# db9smt-autoband.net
KiCad netlist of a schematic drawn in EAGLE
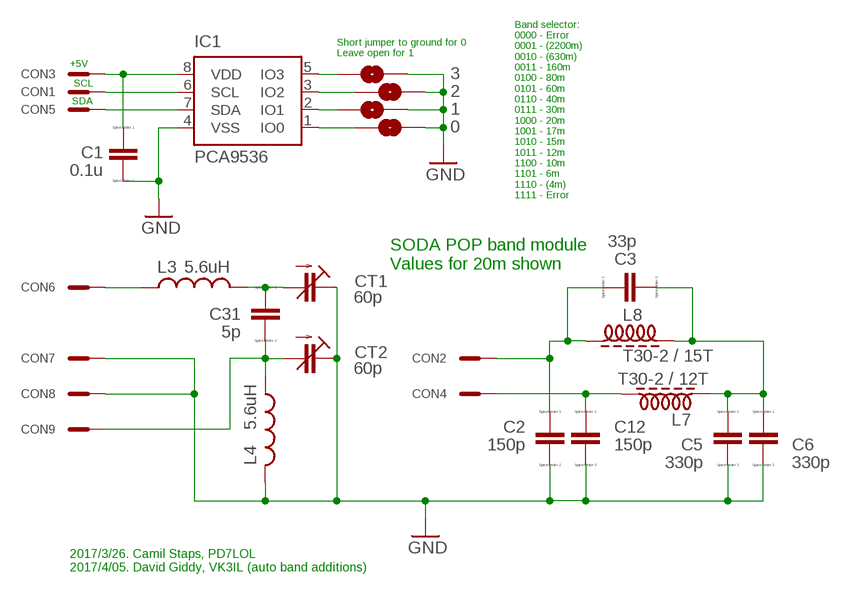
[diagram p0: schematic, sheet 1]

(export (version "E")
  (design (tool "Eeschema 10.0.6"))
  (components
    (comp (ref "0") (value "SJ") (footprint "eagle-import:SJ") (libsource (lib "eagle-import") (part "SJ")))
    (comp (ref "1") (value "SJ") (footprint "eagle-import:SJ") (libsource (lib "eagle-import") (part "SJ")))
    (comp (ref "2") (value "SJ") (footprint "eagle-import:SJ") (libsource (lib "eagle-import") (part "SJ")))
    (comp (ref "3") (value "SJ") (footprint "eagle-import:SJ") (libsource (lib "eagle-import") (part "SJ")))
    (comp (ref "C1")
      (value "0.1u")
      (footprint "eagle-import:C0603")
      (libsource (lib "eagle-import") (part "CC0603"))
    )
    (comp (ref "C2")
      (value "150p")
      (footprint "eagle-import:C0603")
      (libsource (lib "eagle-import") (part "CC0603"))
    )
    (comp (ref "C3")
      (value "33p")
      (footprint "eagle-import:C0603")
      (libsource (lib "eagle-import") (part "CC0603"))
    )
    (comp (ref "C5")
      (value "330p")
      (footprint "eagle-import:C0603")
      (libsource (lib "eagle-import") (part "CC0603"))
    )
    (comp (ref "C6")
      (value "330p")
      (footprint "eagle-import:C0603")
      (libsource (lib "eagle-import") (part "CC0603"))
    )
    (comp (ref "C12")
      (value "150p")
      (footprint "eagle-import:C0603")
      (libsource (lib "eagle-import") (part "CC0603"))
    )
    (comp (ref "C31")
      (value "5p")
      (footprint "eagle-import:C0603")
      (libsource (lib "eagle-import") (part "CC0603"))
    )
    (comp (ref "CON1")
      (value "PADONPRINT")
      (footprint "eagle-import:PAD")
      (libsource (lib "eagle-import") (part "PADONPRINT"))
    )
    (comp (ref "CON2")
      (value "PADONPRINT")
      (footprint "eagle-import:PAD")
      (libsource (lib "eagle-import") (part "PADONPRINT"))
    )
    (comp (ref "CON3")
      (value "PADONPRINT")
      (footprint "eagle-import:PAD")
      (libsource (lib "eagle-import") (part "PADONPRINT"))
    )
    (comp (ref "CON4")
      (value "PADONPRINT")
      (footprint "eagle-import:PAD")
      (libsource (lib "eagle-import") (part "PADONPRINT"))
    )
    (comp (ref "CON5")
      (value "PADONPRINT")
      (footprint "eagle-import:PAD")
      (libsource (lib "eagle-import") (part "PADONPRINT"))
    )
    (comp (ref "CON6")
      (value "PADONPRINT")
      (footprint "eagle-import:PAD")
      (libsource (lib "eagle-import") (part "PADONPRINT"))
    )
    (comp (ref "CON7")
      (value "PADONPRINT")
      (footprint "eagle-import:PAD")
      (libsource (lib "eagle-import") (part "PADONPRINT"))
    )
    (comp (ref "CON8")
      (value "PADONPRINT")
      (footprint "eagle-import:PAD")
      (libsource (lib "eagle-import") (part "PADONPRINT"))
    )
    (comp (ref "CON9")
      (value "PADONPRINT")
      (footprint "eagle-import:PAD")
      (libsource (lib "eagle-import") (part "PADONPRINT"))
    )
    (comp (ref "CT1")
      (value "60p")
      (footprint "eagle-import:CTRIMTZ03")
      (libsource (lib "eagle-import") (part "C-TRIMMTZ03"))
    )
    (comp (ref "CT2")
      (value "60p")
      (footprint "eagle-import:CTRIMTZ03")
      (libsource (lib "eagle-import") (part "C-TRIMMTZ03"))
    )
    (comp (ref "IC1")
      (value "PCA9536")
      (footprint "eagle-import:SO8")
      (libsource (lib "eagle-import") (part "PCA9536"))
    )
    (comp (ref "L3")
      (value "5.6uH")
      (footprint "eagle-import:L2012C")
      (libsource (lib "eagle-import") (part "L-USL2012C"))
    )
    (comp (ref "L4")
      (value "5.6uH")
      (footprint "eagle-import:L2012C")
      (libsource (lib "eagle-import") (part "L-USL2012C"))
    )
    (comp (ref "L7")
      (value "T30-2 / 12T")
      (footprint "eagle-import:T30-2-28AWG-15T")
      (libsource (lib "eagle-import") (part "INDUCTORT30-2-28AWG-15T"))
    )
    (comp (ref "L8")
      (value "T30-2 / 15T")
      (footprint "eagle-import:T30-2-28AWG-15T")
      (libsource (lib "eagle-import") (part "INDUCTORT30-2-28AWG-15T"))
    )
  )
  (nets
    (net (code "1") (name "GND") (class "Default")
      (node (ref "0") (pin "2") (pinfunction "2_2") (pintype "passive"))
      (node (ref "1") (pin "2") (pinfunction "2_2") (pintype "passive"))
      (node (ref "2") (pin "2") (pinfunction "2_2") (pintype "passive"))
      (node (ref "3") (pin "2") (pinfunction "2_2") (pintype "passive"))
      (node (ref "C1") (pin "2") (pinfunction "2_2") (pintype "passive"))
      (node (ref "C12") (pin "2") (pinfunction "2_2") (pintype "passive"))
      (node (ref "C2") (pin "2") (pinfunction "2_2") (pintype "passive"))
      (node (ref "C5") (pin "2") (pinfunction "2_2") (pintype "passive"))
      (node (ref "C6") (pin "2") (pinfunction "2_2") (pintype "passive"))
      (node (ref "CON7") (pin "P$1") (pinfunction "P$1_P$1") (pintype "bidirectional"))
      (node (ref "CON8") (pin "P$1") (pinfunction "P$1_P$1") (pintype "bidirectional"))
      (node (ref "CT1") (pin "1") (pinfunction "E_1") (pintype "passive"))
      (node (ref "CT2") (pin "1") (pinfunction "E_1") (pintype "passive"))
      (node (ref "IC1") (pin "4") (pinfunction "VSS_4") (pintype "power_in"))
      (node (ref "L4") (pin "2") (pinfunction "2_2") (pintype "passive"))
    )
    (net (code "2") (name "Net-(CON6-PadP$1)") (class "Default")
      (node (ref "CON6") (pin "P$1") (pinfunction "P$1_P$1") (pintype "bidirectional"))
      (node (ref "L3") (pin "1") (pinfunction "1_1") (pintype "passive"))
    )
    (net (code "3") (name "Net-(CT1-A)") (class "Default")
      (node (ref "C31") (pin "1") (pinfunction "1_1") (pintype "passive"))
      (node (ref "CT1") (pin "2") (pinfunction "A_2") (pintype "passive"))
      (node (ref "L3") (pin "2") (pinfunction "2_2") (pintype "passive"))
    )
    (net (code "4") (name "Net-(CT2-A)") (class "Default")
      (node (ref "C31") (pin "2") (pinfunction "2_2") (pintype "passive"))
      (node (ref "CON9") (pin "P$1") (pinfunction "P$1_P$1") (pintype "bidirectional"))
      (node (ref "CT2") (pin "2") (pinfunction "A_2") (pintype "passive"))
      (node (ref "L4") (pin "1") (pinfunction "1_1") (pintype "passive"))
    )
    (net (code "5") (name "Net-(IC1-IO0)") (class "Default")
      (node (ref "0") (pin "1") (pinfunction "1_1") (pintype "passive"))
      (node (ref "IC1") (pin "1") (pinfunction "IO0_1") (pintype "bidirectional"))
    )
    (net (code "6") (name "Net-(IC1-IO1)") (class "Default")
      (node (ref "1") (pin "1") (pinfunction "1_1") (pintype "passive"))
      (node (ref "IC1") (pin "2") (pinfunction "IO1_2") (pintype "bidirectional"))
    )
    (net (code "7") (name "Net-(IC1-IO2)") (class "Default")
      (node (ref "2") (pin "1") (pinfunction "1_1") (pintype "passive"))
      (node (ref "IC1") (pin "3") (pinfunction "IO2_3") (pintype "bidirectional"))
    )
    (net (code "8") (name "Net-(IC1-IO3)") (class "Default")
      (node (ref "3") (pin "1") (pinfunction "1_1") (pintype "passive"))
      (node (ref "IC1") (pin "5") (pinfunction "IO3_5") (pintype "bidirectional"))
    )
    (net (code "9") (name "Net-(IC1-SCL)") (class "Default")
      (node (ref "CON1") (pin "P$1") (pinfunction "P$1_P$1") (pintype "bidirectional"))
      (node (ref "IC1") (pin "6") (pinfunction "SCL_6") (pintype "input"))
    )
    (net (code "10") (name "Net-(IC1-SDA)") (class "Default")
      (node (ref "CON5") (pin "P$1") (pinfunction "P$1_P$1") (pintype "bidirectional"))
      (node (ref "IC1") (pin "7") (pinfunction "SDA_7") (pintype "bidirectional"))
    )
    (net (code "11") (name "Net-(IC1-VDD)") (class "Default")
      (node (ref "C1") (pin "1") (pinfunction "1_1") (pintype "passive"))
      (node (ref "CON3") (pin "P$1") (pinfunction "P$1_P$1") (pintype "bidirectional"))
      (node (ref "IC1") (pin "8") (pinfunction "VDD_8") (pintype "power_in"))
    )
    (net (code "12") (name "Net-(L7-1)") (class "Default")
      (node (ref "C3") (pin "2") (pinfunction "2_2") (pintype "passive"))
      (node (ref "C5") (pin "1") (pinfunction "1_1") (pintype "passive"))
      (node (ref "C6") (pin "1") (pinfunction "1_1") (pintype "passive"))
      (node (ref "L7") (pin "P$1") (pinfunction "1_P$1") (pintype "passive"))
      (node (ref "L8") (pin "P$2") (pinfunction "2_P$2") (pintype "passive"))
    )
    (net (code "13") (name "Net-(L7-2)") (class "Default")
      (node (ref "C12") (pin "1") (pinfunction "1_1") (pintype "passive"))
      (node (ref "CON4") (pin "P$1") (pinfunction "P$1_P$1") (pintype "bidirectional"))
      (node (ref "L7") (pin "P$2") (pinfunction "2_P$2") (pintype "passive"))
    )
    (net (code "14") (name "Net-(L8-1)") (class "Default")
      (node (ref "C2") (pin "1") (pinfunction "1_1") (pintype "passive"))
      (node (ref "C3") (pin "1") (pinfunction "1_1") (pintype "passive"))
      (node (ref "CON2") (pin "P$1") (pinfunction "P$1_P$1") (pintype "bidirectional"))
      (node (ref "L8") (pin "P$1") (pinfunction "1_P$1") (pintype "passive"))
    )
  )
)
